# Cansat2019_3279_Container_v01.net
KiCad netlist of a schematic drawn in EAGLE
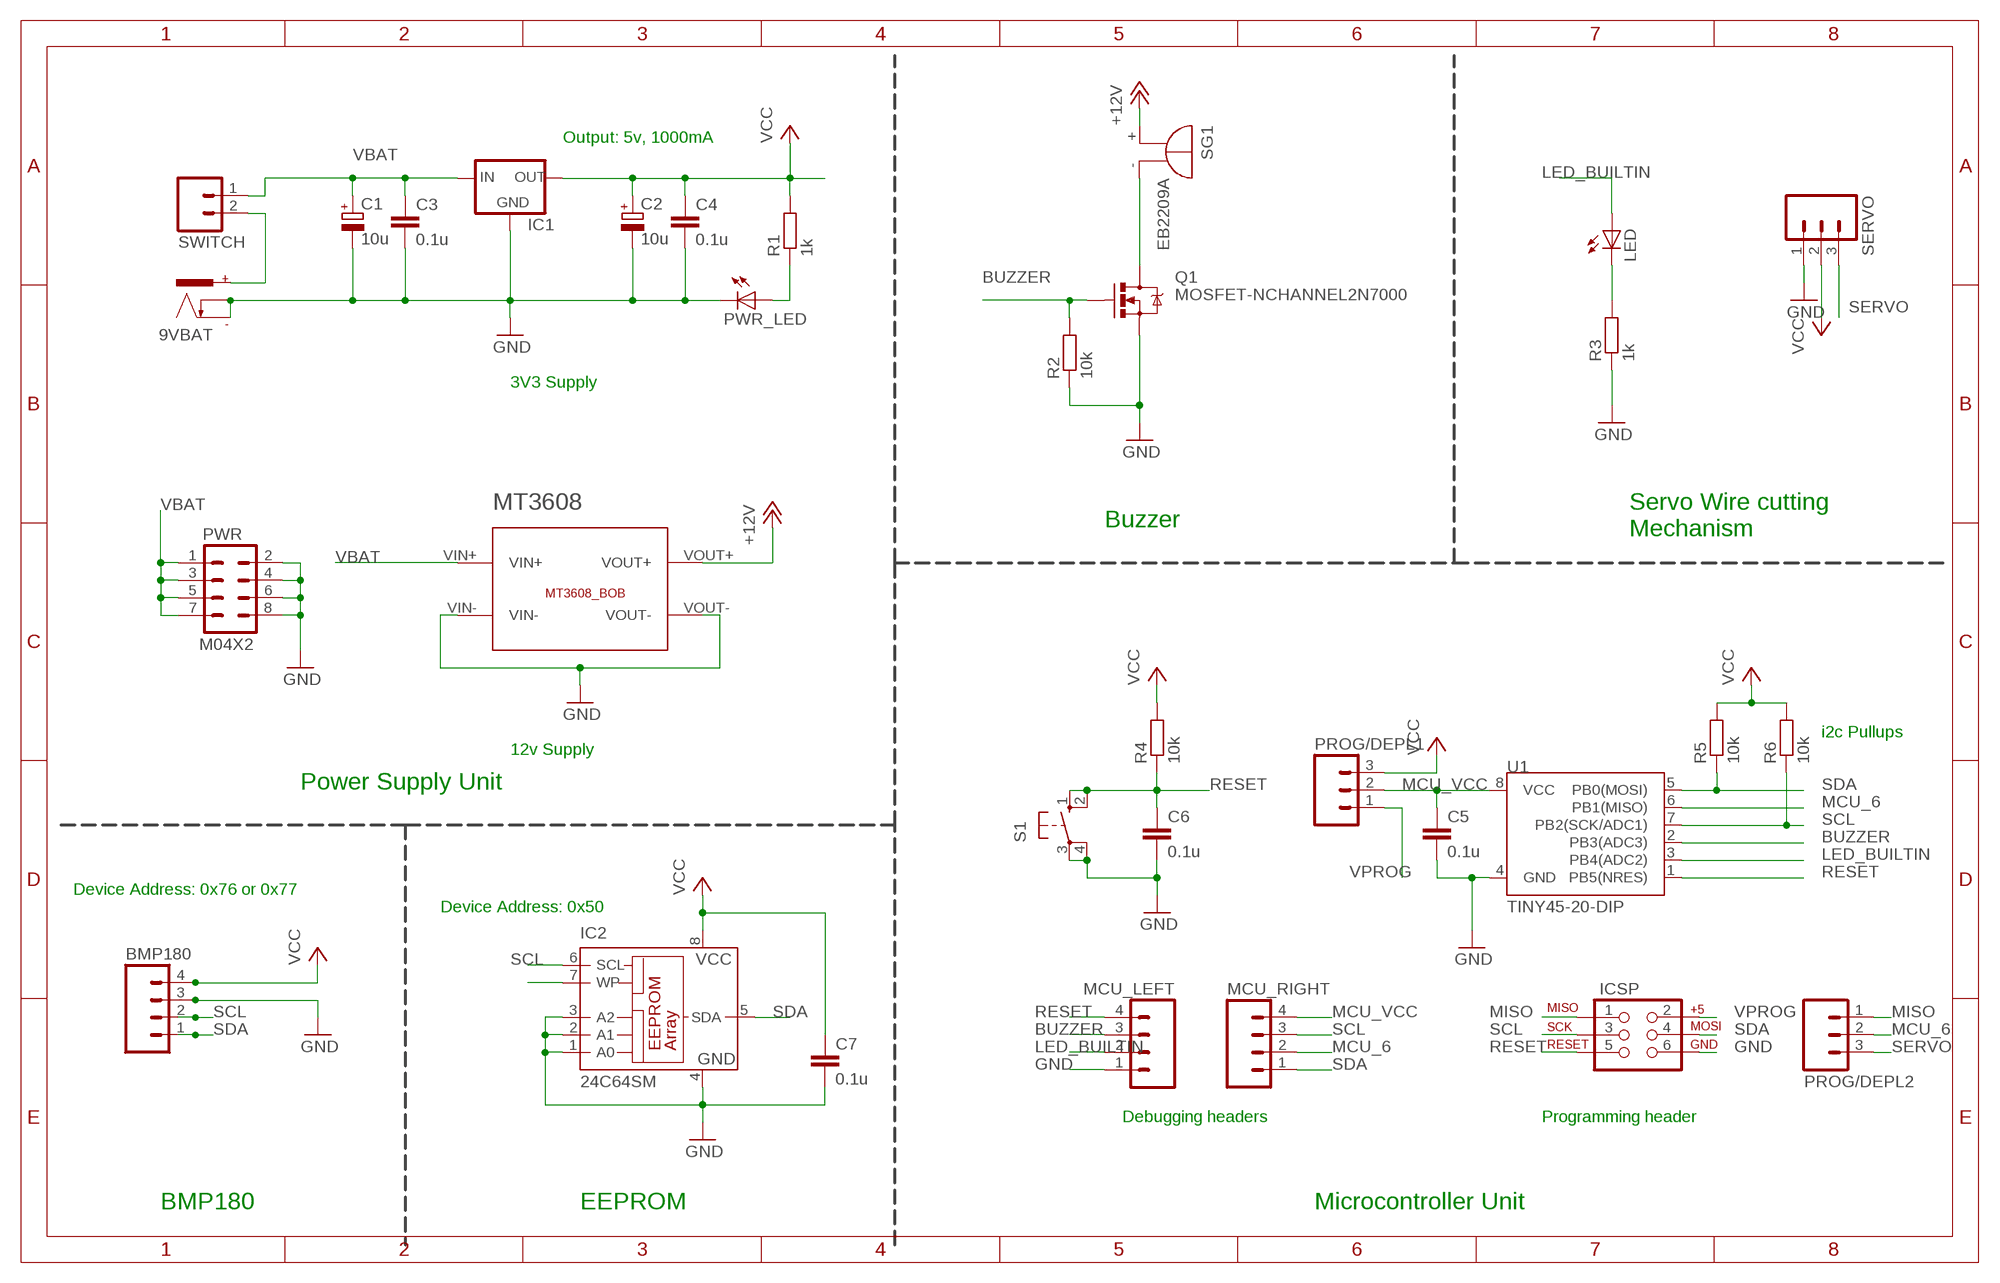
[diagram p0: schematic, sheet 1]

(export (version "E")
  (design (tool "Eeschema 10.0.6"))
  (components
    (comp (ref "9VBAT")
      (value "POWER_CON")
      (footprint "eagle-import:NEB21R")
      (libsource (lib "eagle-import") (part "POWER_CON"))
    )
    (comp (ref "BMP180")
      (value "M04")
      (footprint "eagle-import:04P")
      (libsource (lib "eagle-import") (part "M04"))
    )
    (comp (ref "C1")
      (value "10u")
      (footprint "eagle-import:E2,5-6")
      (libsource (lib "eagle-import") (part "CPOL-EUE2.5-6"))
    )
    (comp (ref "C2")
      (value "10u")
      (footprint "eagle-import:E2,5-6")
      (libsource (lib "eagle-import") (part "CPOL-EUE2.5-6"))
    )
    (comp (ref "C3")
      (value "0.1u")
      (footprint "eagle-import:C025-025X050")
      (libsource (lib "eagle-import") (part "C-EU025-025X050"))
    )
    (comp (ref "C4")
      (value "0.1u")
      (footprint "eagle-import:C025-025X050")
      (libsource (lib "eagle-import") (part "C-EU025-025X050"))
    )
    (comp (ref "C5")
      (value "0.1u")
      (footprint "eagle-import:C025-025X050")
      (libsource (lib "eagle-import") (part "C-EU025-025X050"))
    )
    (comp (ref "C6")
      (value "0.1u")
      (footprint "eagle-import:C025-025X050")
      (libsource (lib "eagle-import") (part "C-EU025-025X050"))
    )
    (comp (ref "C7")
      (value "0.1u")
      (footprint "eagle-import:C025-025X050")
      (libsource (lib "eagle-import") (part "C-EU025-025X050"))
    )
    (comp (ref "IC1")
      (value "V_REG_78XX-TO-220")
      (footprint "eagle-import:TO-220-ALT")
      (libsource (lib "eagle-import") (part "V_REG_78XX-TO-220"))
    )
    (comp (ref "IC2")
      (value "24C64SM")
      (footprint "eagle-import:SO-08M")
      (fields (field (name "MF") "RAMTRON INTERNATIONAL CORP") (field (name "MPN") "FM24C64-S"))
      (libsource (lib "eagle-import") (part "24SMC64"))
    )
    (comp (ref "ICSP")
      (value "AVR_SPI_PRG_6NS")
      (footprint "eagle-import:2X3-NS")
      (libsource (lib "eagle-import") (part "AVR_SPI_PRG_6NS"))
    )
    (comp (ref "LED")
      (value "LED3MM")
      (footprint "eagle-import:LED3MM")
      (libsource (lib "eagle-import") (part "LED3MM"))
    )
    (comp (ref "MCU_LEFT")
      (value "M04")
      (footprint "eagle-import:04P")
      (libsource (lib "eagle-import") (part "M04"))
    )
    (comp (ref "MCU_RIGHT")
      (value "M04")
      (footprint "eagle-import:04P")
      (libsource (lib "eagle-import") (part "M04"))
    )
    (comp (ref "MT3608")
      (value "MT3608_BOB")
      (footprint "eagle-import:MT3608_BOB")
      (libsource (lib "eagle-import") (part "MT3608_BOB"))
    )
    (comp (ref "PROG/DEPL1")
      (value "M03PTH")
      (footprint "eagle-import:1X03")
      (libsource (lib "eagle-import") (part "M03PTH"))
    )
    (comp (ref "PROG/DEPL2")
      (value "M03PTH")
      (footprint "eagle-import:1X03")
      (libsource (lib "eagle-import") (part "M03PTH"))
    )
    (comp (ref "PWR")
      (value "M04X2")
      (footprint "eagle-import:2X4")
      (libsource (lib "eagle-import") (part "M04X2"))
    )
    (comp (ref "PWR_LED")
      (value "LED3MM")
      (footprint "eagle-import:LED3MM")
      (libsource (lib "eagle-import") (part "LED3MM"))
    )
    (comp (ref "Q1")
      (value "MOSFET-NCHANNEL2N7000")
      (footprint "eagle-import:TO-92")
      (libsource (lib "eagle-import") (part "MOSFET-NCHANNEL2N7000"))
    )
    (comp (ref "R1")
      (value "1k")
      (footprint "eagle-import:0204_7")
      (libsource (lib "eagle-import") (part "R-EU_0204/7"))
    )
    (comp (ref "R2")
      (value "10k")
      (footprint "eagle-import:0204_7")
      (libsource (lib "eagle-import") (part "R-EU_0204/7"))
    )
    (comp (ref "R3")
      (value "1k")
      (footprint "eagle-import:0204_7")
      (libsource (lib "eagle-import") (part "R-EU_0204/7"))
    )
    (comp (ref "R4")
      (value "10k")
      (footprint "eagle-import:0204_7")
      (libsource (lib "eagle-import") (part "R-EU_0204/7"))
    )
    (comp (ref "R5")
      (value "10k")
      (footprint "eagle-import:0204_7")
      (libsource (lib "eagle-import") (part "R-EU_0204/7"))
    )
    (comp (ref "R6")
      (value "10k")
      (footprint "eagle-import:0204_7")
      (libsource (lib "eagle-import") (part "R-EU_0204/7"))
    )
    (comp (ref "S1")
      (value "PUSH-BUTTON-6MM")
      (footprint "eagle-import:B3F-10XX")
      (libsource (lib "eagle-import") (part "PUSH-BUTTON-6MM"))
    )
    (comp (ref "SERVO")
      (value "M03")
      (footprint "eagle-import:03P")
      (libsource (lib "eagle-import") (part "M03"))
    )
    (comp (ref "SG1")
      (value "EB2209A")
      (footprint "eagle-import:EB2209A")
      (libsource (lib "eagle-import") (part "EB2209A"))
    )
    (comp (ref "SWITCH")
      (value "M02")
      (footprint "eagle-import:02P")
      (libsource (lib "eagle-import") (part "M02"))
    )
    (comp (ref "U1")
      (value "TINY45-20-DIP")
      (footprint "eagle-import:DIP08")
      (libsource (lib "eagle-import") (part "ATTINY45TINY45-20-DIP"))
    )
  )
  (nets
    (net (code "1") (name "+12V") (class "Default")
      (node (ref "MT3608") (pin "VOUT+") (pinfunction "VOUT+_VOUT+") (pintype "bidirectional"))
      (node (ref "SG1") (pin "+") (pinfunction "+_+") (pintype "passive"))
    )
    (net (code "2") (name "/BUZZER") (class "Default")
      (node (ref "MCU_LEFT") (pin "3") (pinfunction "3_3") (pintype "passive"))
      (node (ref "Q1") (pin "2") (pinfunction "G_2") (pintype "passive"))
      (node (ref "R2") (pin "2") (pinfunction "2_2") (pintype "passive"))
      (node (ref "U1") (pin "2") (pinfunction "PB3(ADC3)_2") (pintype "bidirectional"))
    )
    (net (code "3") (name "/LED_BUILTIN") (class "Default")
      (node (ref "LED") (pin "A") (pinfunction "A_A") (pintype "passive"))
      (node (ref "MCU_LEFT") (pin "2") (pinfunction "2_2") (pintype "passive"))
      (node (ref "U1") (pin "3") (pinfunction "PB4(ADC2)_3") (pintype "bidirectional"))
    )
    (net (code "4") (name "/MCU_6") (class "Default")
      (node (ref "MCU_RIGHT") (pin "2") (pinfunction "2_2") (pintype "passive"))
      (node (ref "PROG/DEPL2") (pin "2") (pinfunction "2_2") (pintype "passive"))
      (node (ref "U1") (pin "6") (pinfunction "PB1(MISO)_6") (pintype "bidirectional"))
    )
    (net (code "5") (name "/MCU_VCC") (class "Default")
      (node (ref "C5") (pin "1") (pinfunction "1_1") (pintype "passive"))
      (node (ref "MCU_RIGHT") (pin "4") (pinfunction "4_4") (pintype "passive"))
      (node (ref "PROG/DEPL1") (pin "2") (pinfunction "2_2") (pintype "passive"))
      (node (ref "U1") (pin "8") (pinfunction "VCC_8") (pintype "bidirectional"))
    )
    (net (code "6") (name "/MISO") (class "Default")
      (node (ref "ICSP") (pin "1") (pinfunction "1_1") (pintype "passive"))
      (node (ref "PROG/DEPL2") (pin "1") (pinfunction "1_1") (pintype "passive"))
    )
    (net (code "7") (name "/RESET") (class "Default")
      (node (ref "C6") (pin "1") (pinfunction "1_1") (pintype "passive"))
      (node (ref "ICSP") (pin "5") (pinfunction "5_5") (pintype "passive"))
      (node (ref "MCU_LEFT") (pin "4") (pinfunction "4_4") (pintype "passive"))
      (node (ref "R4") (pin "1") (pinfunction "1_1") (pintype "passive"))
      (node (ref "S1") (pin "1") (pinfunction "S_1") (pintype "passive"))
      (node (ref "S1") (pin "2") (pinfunction "S1_2") (pintype "passive"))
      (node (ref "U1") (pin "1") (pinfunction "PB5(NRES)_1") (pintype "bidirectional"))
    )
    (net (code "8") (name "/SCL") (class "Default")
      (node (ref "BMP180") (pin "2") (pinfunction "2_2") (pintype "passive"))
      (node (ref "IC2") (pin "6") (pinfunction "SCL_6") (pintype "input"))
      (node (ref "ICSP") (pin "3") (pinfunction "3_3") (pintype "passive"))
      (node (ref "MCU_RIGHT") (pin "3") (pinfunction "3_3") (pintype "passive"))
      (node (ref "R6") (pin "1") (pinfunction "1_1") (pintype "passive"))
      (node (ref "U1") (pin "7") (pinfunction "PB2(SCK/ADC1)_7") (pintype "bidirectional"))
    )
    (net (code "9") (name "/SDA") (class "Default")
      (node (ref "BMP180") (pin "1") (pinfunction "1_1") (pintype "passive"))
      (node (ref "IC2") (pin "5") (pinfunction "SDA_5") (pintype "bidirectional"))
      (node (ref "ICSP") (pin "4") (pinfunction "4_4") (pintype "passive"))
      (node (ref "MCU_RIGHT") (pin "1") (pinfunction "1_1") (pintype "passive"))
      (node (ref "R5") (pin "1") (pinfunction "1_1") (pintype "passive"))
      (node (ref "U1") (pin "5") (pinfunction "PB0(MOSI)_5") (pintype "bidirectional"))
    )
    (net (code "10") (name "/SERVO") (class "Default")
      (node (ref "PROG/DEPL2") (pin "3") (pinfunction "3_3") (pintype "passive"))
      (node (ref "SERVO") (pin "3") (pinfunction "3_3") (pintype "passive"))
    )
    (net (code "11") (name "/VBAT") (class "Default")
      (node (ref "C1") (pin "+") (pinfunction "+_+") (pintype "passive"))
      (node (ref "C3") (pin "1") (pinfunction "1_1") (pintype "passive"))
      (node (ref "IC1") (pin "IN") (pinfunction "IN_IN") (pintype "input"))
      (node (ref "MT3608") (pin "VIN+") (pinfunction "VIN+_VIN+") (pintype "bidirectional"))
      (node (ref "PWR") (pin "1") (pinfunction "1_1") (pintype "passive"))
      (node (ref "PWR") (pin "3") (pinfunction "3_3") (pintype "passive"))
      (node (ref "PWR") (pin "5") (pinfunction "5_5") (pintype "passive"))
      (node (ref "PWR") (pin "7") (pinfunction "7_7") (pintype "passive"))
      (node (ref "SWITCH") (pin "1") (pinfunction "1_1") (pintype "passive"))
    )
    (net (code "12") (name "/VPROG") (class "Default")
      (node (ref "ICSP") (pin "2") (pinfunction "2_2") (pintype "passive"))
      (node (ref "PROG/DEPL1") (pin "1") (pinfunction "1_1") (pintype "passive"))
    )
    (net (code "13") (name "GND") (class "Default")
      (node (ref "9VBAT") (pin "-") (pinfunction "-_-") (pintype "passive"))
      (node (ref "9VBAT") (pin "C") (pinfunction "C_C") (pintype "passive"))
      (node (ref "BMP180") (pin "3") (pinfunction "3_3") (pintype "passive"))
      (node (ref "C1") (pin "-") (pinfunction "-_-") (pintype "passive"))
      (node (ref "C2") (pin "-") (pinfunction "-_-") (pintype "passive"))
      (node (ref "C3") (pin "2") (pinfunction "2_2") (pintype "passive"))
      (node (ref "C4") (pin "2") (pinfunction "2_2") (pintype "passive"))
      (node (ref "C5") (pin "2") (pinfunction "2_2") (pintype "passive"))
      (node (ref "C6") (pin "2") (pinfunction "2_2") (pintype "passive"))
      (node (ref "C7") (pin "2") (pinfunction "2_2") (pintype "passive"))
      (node (ref "IC1") (pin "GND") (pinfunction "GND_GND") (pintype "input"))
      (node (ref "IC2") (pin "1") (pinfunction "A0_1") (pintype "input"))
      (node (ref "IC2") (pin "2") (pinfunction "A1_2") (pintype "input"))
      (node (ref "IC2") (pin "3") (pinfunction "A2_3") (pintype "input"))
      (node (ref "IC2") (pin "4") (pinfunction "GND_4") (pintype "power_in"))
      (node (ref "ICSP") (pin "6") (pinfunction "6_6") (pintype "passive"))
      (node (ref "MCU_LEFT") (pin "1") (pinfunction "1_1") (pintype "passive"))
      (node (ref "MT3608") (pin "VIN-") (pinfunction "VIN-_VIN-") (pintype "bidirectional"))
      (node (ref "MT3608") (pin "VOUT-") (pinfunction "VOUT-_VOUT-") (pintype "bidirectional"))
      (node (ref "PWR") (pin "2") (pinfunction "2_2") (pintype "passive"))
      (node (ref "PWR") (pin "4") (pinfunction "4_4") (pintype "passive"))
      (node (ref "PWR") (pin "6") (pinfunction "6_6") (pintype "passive"))
      (node (ref "PWR") (pin "8") (pinfunction "8_8") (pintype "passive"))
      (node (ref "PWR_LED") (pin "K") (pinfunction "C_K") (pintype "passive"))
      (node (ref "Q1") (pin "1") (pinfunction "S_1") (pintype "passive"))
      (node (ref "R2") (pin "1") (pinfunction "1_1") (pintype "passive"))
      (node (ref "R3") (pin "1") (pinfunction "1_1") (pintype "passive"))
      (node (ref "S1") (pin "3") (pinfunction "P_3") (pintype "passive"))
      (node (ref "S1") (pin "4") (pinfunction "P1_4") (pintype "passive"))
      (node (ref "SERVO") (pin "1") (pinfunction "1_1") (pintype "passive"))
      (node (ref "U1") (pin "4") (pinfunction "GND_4") (pintype "bidirectional"))
    )
    (net (code "14") (name "Net-(9VBAT-Pad+)") (class "Default")
      (node (ref "9VBAT") (pin "+") (pinfunction "+_+") (pintype "passive"))
      (node (ref "SWITCH") (pin "2") (pinfunction "2_2") (pintype "passive"))
    )
    (net (code "15") (name "Net-(LED-C)") (class "Default")
      (node (ref "LED") (pin "K") (pinfunction "C_K") (pintype "passive"))
      (node (ref "R3") (pin "2") (pinfunction "2_2") (pintype "passive"))
    )
    (net (code "16") (name "Net-(PWR_LED-PadA)") (class "Default")
      (node (ref "PWR_LED") (pin "A") (pinfunction "A_A") (pintype "passive"))
      (node (ref "R1") (pin "1") (pinfunction "1_1") (pintype "passive"))
    )
    (net (code "17") (name "Net-(Q1-D)") (class "Default")
      (node (ref "Q1") (pin "3") (pinfunction "D_3") (pintype "passive"))
      (node (ref "SG1") (pin "-") (pinfunction "-_-") (pintype "passive"))
    )
    (net (code "18") (name "VCC") (class "Default")
      (node (ref "BMP180") (pin "4") (pinfunction "4_4") (pintype "passive"))
      (node (ref "C2") (pin "+") (pinfunction "+_+") (pintype "passive"))
      (node (ref "C4") (pin "1") (pinfunction "1_1") (pintype "passive"))
      (node (ref "C7") (pin "1") (pinfunction "1_1") (pintype "passive"))
      (node (ref "IC1") (pin "OUT") (pinfunction "OUT_OUT") (pintype "output"))
      (node (ref "IC2") (pin "8") (pinfunction "VCC_8") (pintype "power_in"))
      (node (ref "PROG/DEPL1") (pin "3") (pinfunction "3_3") (pintype "passive"))
      (node (ref "R1") (pin "2") (pinfunction "2_2") (pintype "passive"))
      (node (ref "R4") (pin "2") (pinfunction "2_2") (pintype "passive"))
      (node (ref "R5") (pin "2") (pinfunction "2_2") (pintype "passive"))
      (node (ref "R6") (pin "2") (pinfunction "2_2") (pintype "passive"))
      (node (ref "SERVO") (pin "2") (pinfunction "2_2") (pintype "passive"))
    )
    (net (code "19") (name "unconnected-(IC2-WP-Pad7)") (class "Default")
      (node (ref "IC2") (pin "7") (pinfunction "WP_7") (pintype "input"))
    )
  )
)
